# Sheet2.net
KiCad netlist of a schematic drawn in Altium Designer
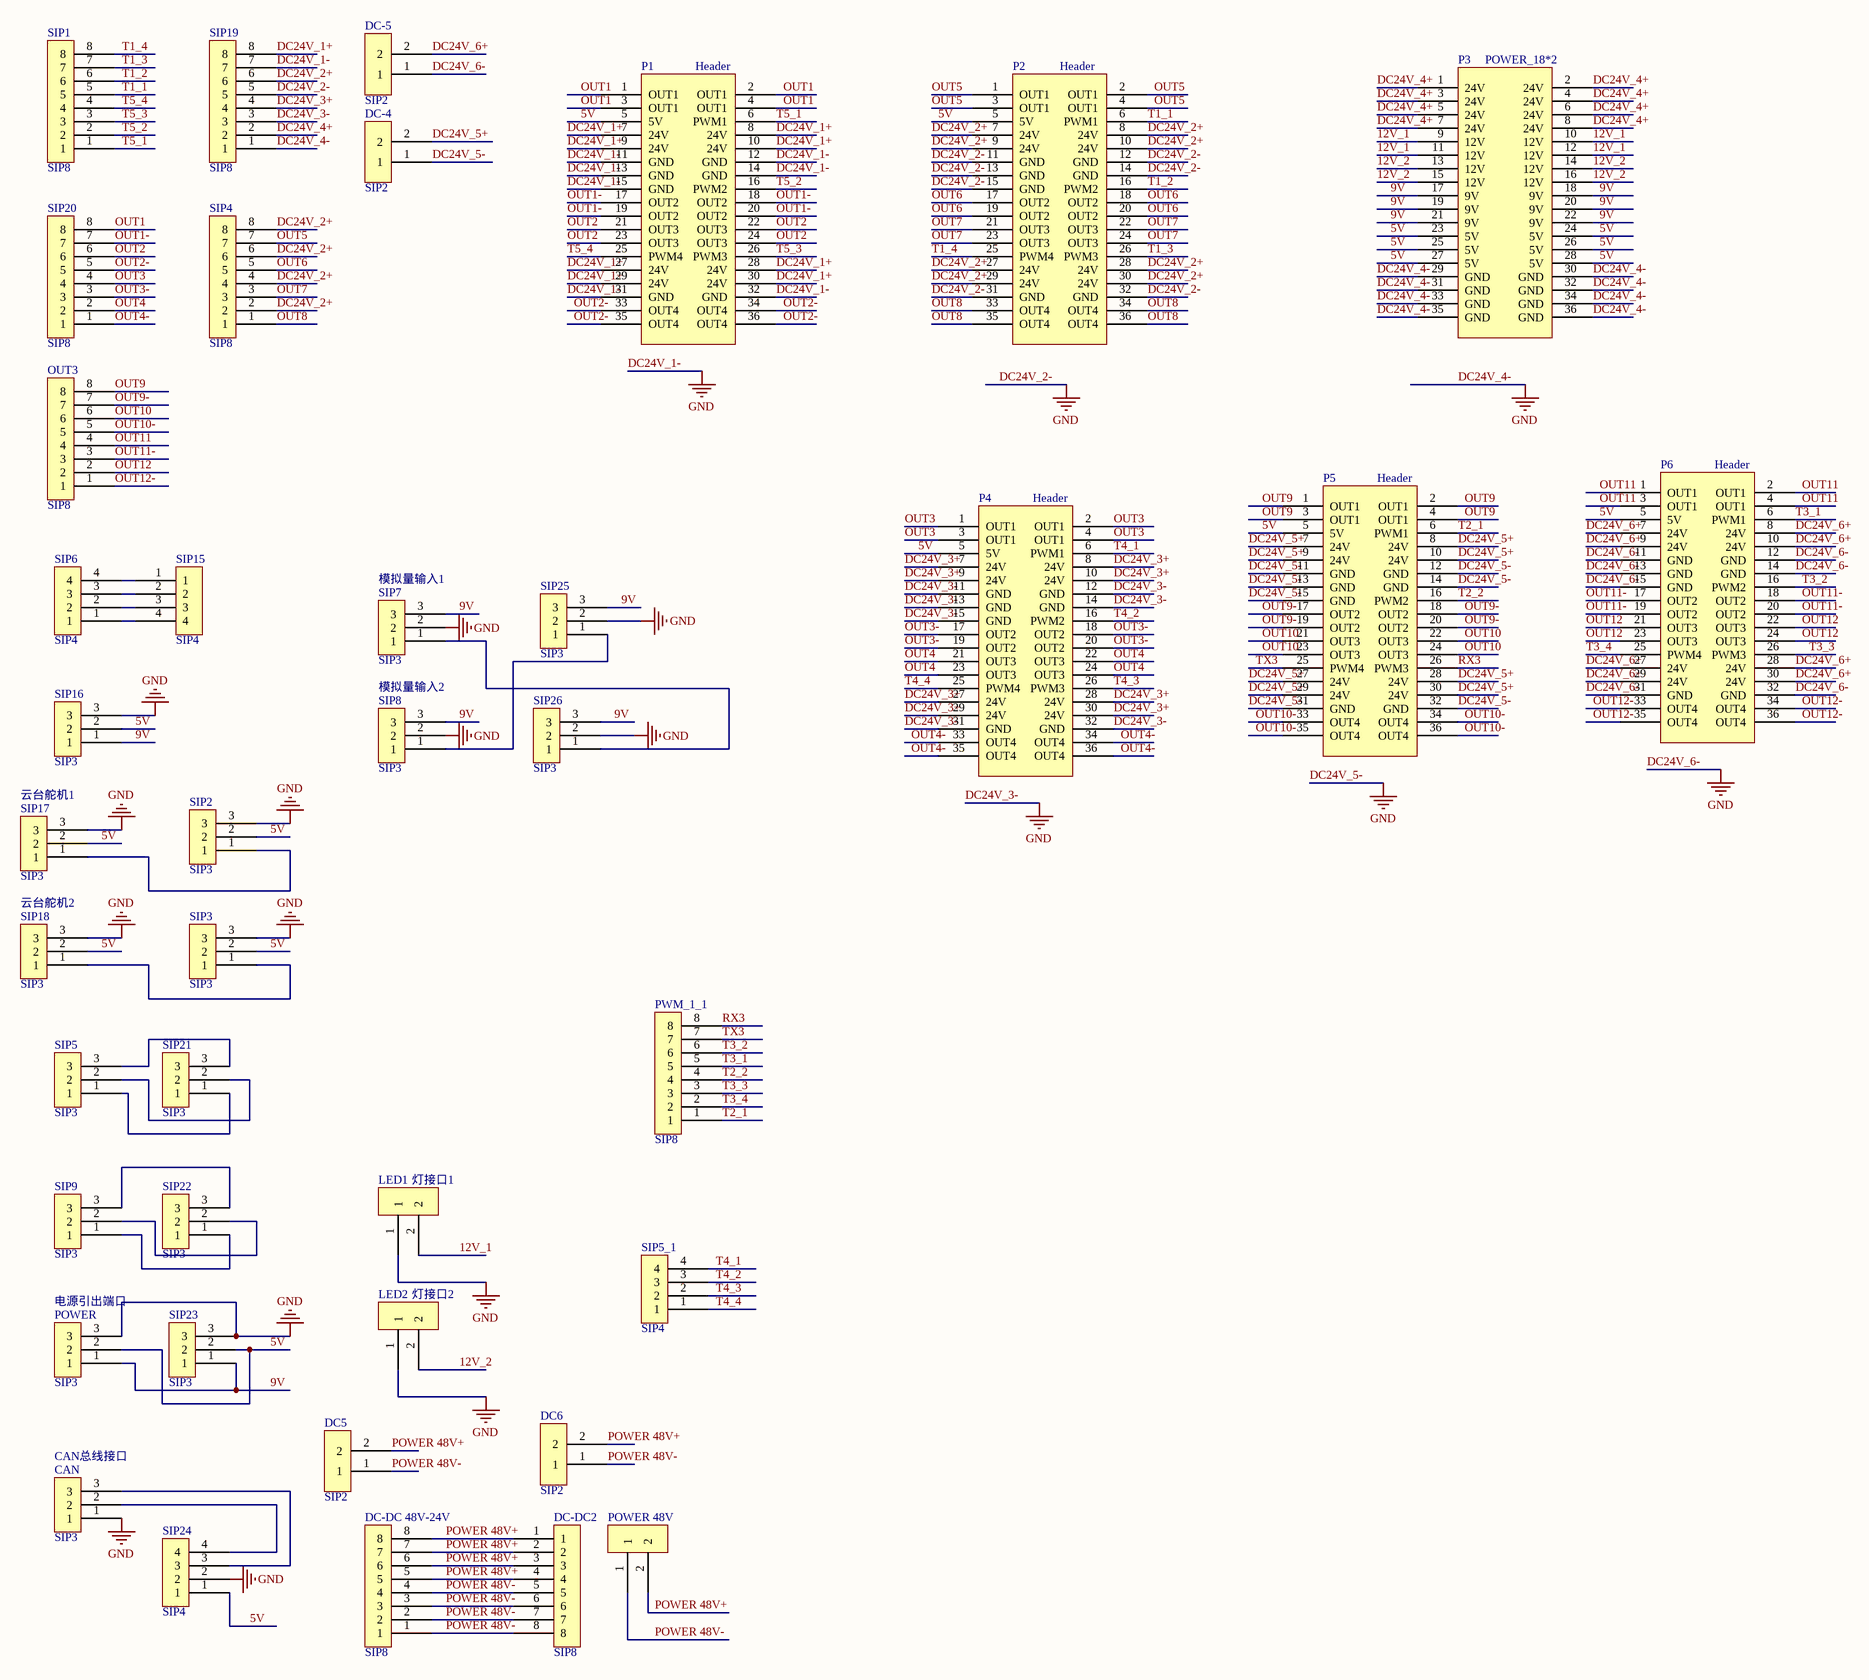
[diagram p0: Sheet2.SchDoc]

(export (version "E")
  (design (tool "Eeschema 10.0.6"))
  (components
    (comp (ref "CAN") (value "SIP3") (footprint "SIP3") (libsource (lib "qudong") (part "SIP3")))
    (comp (ref "DC-4") (value "SIP2") (footprint "DIP2-3MM-K") (libsource (lib "qudong") (part "SIP2")))
    (comp (ref "DC-5") (value "SIP2") (footprint "DIP2-3MM-K") (libsource (lib "qudong") (part "SIP2")))
    (comp (ref "DC-DC 48V-24V")
      (value "SIP8")
      (footprint "DIP8-3MM")
      (libsource (lib "qudong") (part "SIP8"))
    )
    (comp (ref "DC-DC2") (value "SIP8") (footprint "DIP8-3MM") (libsource (lib "") (part "SIP8_1")))
    (comp (ref "DC5") (value "SIP2") (footprint "DIP2-3MM-K") (libsource (lib "qudong") (part "SIP2")))
    (comp (ref "DC6") (value "SIP2") (footprint "DIP2-3MM-K") (libsource (lib "qudong") (part "SIP2")))
    (comp (ref "LED1") (value "SIP2") (footprint "SIP2-3MM") (libsource (lib "") (part "SIP2_1")))
    (comp (ref "LED2") (value "SIP2") (footprint "SIP2-3MM") (libsource (lib "") (part "SIP2_1")))
    (comp (ref "OUT3") (value "SIP8") (footprint "DIP8-3MM") (libsource (lib "qudong") (part "SIP8")))
    (comp (ref "P1") (value "Header") (footprint "DIP36-3.96MM") (libsource (lib "qudong") (part "Header")))
    (comp (ref "P2") (value "Header") (footprint "DIP36-3.96MM") (libsource (lib "qudong") (part "Header")))
    (comp (ref "P3")
      (value "POWER_18*2")
      (footprint "DIP36-3.96MM")
      (libsource (lib "qudong") (part "POWER_18*2"))
    )
    (comp (ref "P4") (value "Header") (footprint "DIP36-3.96MM") (libsource (lib "qudong") (part "Header")))
    (comp (ref "P5") (value "Header") (footprint "DIP36-3.96MM") (libsource (lib "qudong") (part "Header")))
    (comp (ref "P6") (value "Header") (footprint "DIP36-3.96MM") (libsource (lib "qudong") (part "Header")))
    (comp (ref "POWER") (value "SIP3") (footprint "SIP3") (libsource (lib "qudong") (part "SIP3")))
    (comp (ref "POWER 48V") (value "SIP2") (footprint "SIP2-3MM") (libsource (lib "") (part "SIP2_1")))
    (comp (ref "PWM_1_1") (value "SIP8") (footprint "SIP8") (libsource (lib "qudong") (part "SIP8")))
    (comp (ref "SIP1") (value "SIP8") (footprint "SIP8") (libsource (lib "qudong") (part "SIP8")))
    (comp (ref "SIP2") (value "SIP3") (footprint "SIP3") (libsource (lib "qudong") (part "SIP3")))
    (comp (ref "SIP3") (value "SIP3") (footprint "SIP3") (libsource (lib "qudong") (part "SIP3")))
    (comp (ref "SIP4") (value "SIP8") (footprint "DIP8-3MM") (libsource (lib "qudong") (part "SIP8")))
    (comp (ref "SIP5") (value "SIP3") (footprint "SIP3") (libsource (lib "qudong") (part "SIP3")))
    (comp (ref "SIP5_1") (value "SIP4") (footprint "SIP4") (libsource (lib "qudong") (part "SIP4")))
    (comp (ref "SIP6") (value "SIP4") (footprint "SIP4") (libsource (lib "qudong") (part "SIP4")))
    (comp (ref "SIP7") (value "SIP3") (footprint "SIP3") (libsource (lib "qudong") (part "SIP3")))
    (comp (ref "SIP8") (value "SIP3") (footprint "SIP3") (libsource (lib "qudong") (part "SIP3")))
    (comp (ref "SIP9") (value "SIP3") (footprint "SIP3") (libsource (lib "qudong") (part "SIP3")))
    (comp (ref "SIP15") (value "SIP4") (footprint "SIP4") (libsource (lib "") (part "SIP4_1")))
    (comp (ref "SIP16") (value "SIP3") (footprint "SIP3") (libsource (lib "qudong") (part "SIP3")))
    (comp (ref "SIP17") (value "SIP3") (footprint "SIP3") (libsource (lib "qudong") (part "SIP3")))
    (comp (ref "SIP18") (value "SIP3") (footprint "SIP3") (libsource (lib "qudong") (part "SIP3")))
    (comp (ref "SIP19") (value "SIP8") (footprint "DIP8-3MM") (libsource (lib "qudong") (part "SIP8")))
    (comp (ref "SIP20") (value "SIP8") (footprint "DIP8-3MM") (libsource (lib "qudong") (part "SIP8")))
    (comp (ref "SIP21") (value "SIP3") (footprint "SIP3") (libsource (lib "qudong") (part "SIP3")))
    (comp (ref "SIP22") (value "SIP3") (footprint "SIP3") (libsource (lib "qudong") (part "SIP3")))
    (comp (ref "SIP23") (value "SIP3") (footprint "SIP3") (libsource (lib "qudong") (part "SIP3")))
    (comp (ref "SIP24") (value "SIP4") (footprint "SIP4") (libsource (lib "qudong") (part "SIP4")))
    (comp (ref "SIP25") (value "SIP3") (footprint "SIP3") (libsource (lib "qudong") (part "SIP3")))
    (comp (ref "SIP26") (value "SIP3") (footprint "SIP3") (libsource (lib "qudong") (part "SIP3")))
  )
  (nets
    (net (code "1") (name "/5V") (class "Default")
      (node (ref "P1") (pin "5") (pinfunction "5V_5") (pintype "passive"))
      (node (ref "P2") (pin "5") (pinfunction "5V_5") (pintype "passive"))
      (node (ref "P3") (pin "23") (pinfunction "5V_23") (pintype "passive"))
      (node (ref "P3") (pin "24") (pinfunction "5V_24") (pintype "passive"))
      (node (ref "P3") (pin "25") (pinfunction "5V_25") (pintype "passive"))
      (node (ref "P3") (pin "26") (pinfunction "5V_26") (pintype "passive"))
      (node (ref "P3") (pin "27") (pinfunction "5V_27") (pintype "passive"))
      (node (ref "P3") (pin "28") (pinfunction "5V_28") (pintype "passive"))
      (node (ref "P4") (pin "5") (pinfunction "5V_5") (pintype "passive"))
      (node (ref "P5") (pin "5") (pinfunction "5V_5") (pintype "passive"))
      (node (ref "P6") (pin "5") (pinfunction "5V_5") (pintype "passive"))
      (node (ref "POWER") (pin "2") (pinfunction "2_2") (pintype "passive"))
      (node (ref "SIP16") (pin "2") (pinfunction "2_2") (pintype "passive"))
      (node (ref "SIP17") (pin "2") (pinfunction "2_2") (pintype "passive"))
      (node (ref "SIP18") (pin "2") (pinfunction "2_2") (pintype "passive"))
      (node (ref "SIP2") (pin "2") (pinfunction "2_2") (pintype "passive"))
      (node (ref "SIP23") (pin "2") (pinfunction "2_2") (pintype "passive"))
      (node (ref "SIP24") (pin "1") (pinfunction "1_1") (pintype "passive"))
      (node (ref "SIP3") (pin "2") (pinfunction "2_2") (pintype "passive"))
    )
    (net (code "2") (name "/9V") (class "Default")
      (node (ref "P3") (pin "17") (pinfunction "9V_17") (pintype "passive"))
      (node (ref "P3") (pin "18") (pinfunction "9V_18") (pintype "passive"))
      (node (ref "P3") (pin "19") (pinfunction "9V_19") (pintype "passive"))
      (node (ref "P3") (pin "20") (pinfunction "9V_20") (pintype "passive"))
      (node (ref "P3") (pin "21") (pinfunction "9V_21") (pintype "passive"))
      (node (ref "P3") (pin "22") (pinfunction "9V_22") (pintype "passive"))
      (node (ref "POWER") (pin "1") (pinfunction "1_1") (pintype "passive"))
      (node (ref "SIP16") (pin "1") (pinfunction "1_1") (pintype "passive"))
      (node (ref "SIP23") (pin "1") (pinfunction "1_1") (pintype "passive"))
      (node (ref "SIP25") (pin "3") (pinfunction "3_3") (pintype "passive"))
      (node (ref "SIP26") (pin "3") (pinfunction "3_3") (pintype "passive"))
      (node (ref "SIP7") (pin "3") (pinfunction "3_3") (pintype "passive"))
      (node (ref "SIP8") (pin "3") (pinfunction "3_3") (pintype "passive"))
    )
    (net (code "3") (name "/12V_1") (class "Default")
      (node (ref "LED1") (pin "2") (pinfunction "2_2") (pintype "passive"))
      (node (ref "P3") (pin "10") (pinfunction "12V_10") (pintype "passive"))
      (node (ref "P3") (pin "11") (pinfunction "12V_11") (pintype "passive"))
      (node (ref "P3") (pin "12") (pinfunction "12V_12") (pintype "passive"))
      (node (ref "P3") (pin "9") (pinfunction "12V_9") (pintype "passive"))
    )
    (net (code "4") (name "/12V_2") (class "Default")
      (node (ref "LED2") (pin "2") (pinfunction "2_2") (pintype "passive"))
      (node (ref "P3") (pin "13") (pinfunction "12V_13") (pintype "passive"))
      (node (ref "P3") (pin "14") (pinfunction "12V_14") (pintype "passive"))
      (node (ref "P3") (pin "15") (pinfunction "12V_15") (pintype "passive"))
      (node (ref "P3") (pin "16") (pinfunction "12V_16") (pintype "passive"))
    )
    (net (code "5") (name "/DC24V_1+") (class "Default")
      (node (ref "P1") (pin "10") (pinfunction "24V_10") (pintype "passive"))
      (node (ref "P1") (pin "27") (pinfunction "24V_27") (pintype "passive"))
      (node (ref "P1") (pin "28") (pinfunction "24V_28") (pintype "passive"))
      (node (ref "P1") (pin "29") (pinfunction "24V_29") (pintype "passive"))
      (node (ref "P1") (pin "30") (pinfunction "24V_30") (pintype "passive"))
      (node (ref "P1") (pin "7") (pinfunction "24V_7") (pintype "passive"))
      (node (ref "P1") (pin "8") (pinfunction "24V_8") (pintype "passive"))
      (node (ref "P1") (pin "9") (pinfunction "24V_9") (pintype "passive"))
      (node (ref "SIP19") (pin "8") (pinfunction "8_8") (pintype "passive"))
    )
    (net (code "6") (name "/DC24V_2+") (class "Default")
      (node (ref "P2") (pin "10") (pinfunction "24V_10") (pintype "passive"))
      (node (ref "P2") (pin "27") (pinfunction "24V_27") (pintype "passive"))
      (node (ref "P2") (pin "28") (pinfunction "24V_28") (pintype "passive"))
      (node (ref "P2") (pin "29") (pinfunction "24V_29") (pintype "passive"))
      (node (ref "P2") (pin "30") (pinfunction "24V_30") (pintype "passive"))
      (node (ref "P2") (pin "7") (pinfunction "24V_7") (pintype "passive"))
      (node (ref "P2") (pin "8") (pinfunction "24V_8") (pintype "passive"))
      (node (ref "P2") (pin "9") (pinfunction "24V_9") (pintype "passive"))
      (node (ref "SIP19") (pin "6") (pinfunction "6_6") (pintype "passive"))
      (node (ref "SIP4") (pin "2") (pinfunction "2_2") (pintype "passive"))
      (node (ref "SIP4") (pin "4") (pinfunction "4_4") (pintype "passive"))
      (node (ref "SIP4") (pin "6") (pinfunction "6_6") (pintype "passive"))
      (node (ref "SIP4") (pin "8") (pinfunction "8_8") (pintype "passive"))
    )
    (net (code "7") (name "/DC24V_3+") (class "Default")
      (node (ref "P4") (pin "10") (pinfunction "24V_10") (pintype "passive"))
      (node (ref "P4") (pin "27") (pinfunction "24V_27") (pintype "passive"))
      (node (ref "P4") (pin "28") (pinfunction "24V_28") (pintype "passive"))
      (node (ref "P4") (pin "29") (pinfunction "24V_29") (pintype "passive"))
      (node (ref "P4") (pin "30") (pinfunction "24V_30") (pintype "passive"))
      (node (ref "P4") (pin "7") (pinfunction "24V_7") (pintype "passive"))
      (node (ref "P4") (pin "8") (pinfunction "24V_8") (pintype "passive"))
      (node (ref "P4") (pin "9") (pinfunction "24V_9") (pintype "passive"))
      (node (ref "SIP19") (pin "4") (pinfunction "4_4") (pintype "passive"))
    )
    (net (code "8") (name "/DC24V_4+") (class "Default")
      (node (ref "P3") (pin "1") (pinfunction "24V_1") (pintype "passive"))
      (node (ref "P3") (pin "2") (pinfunction "24V_2") (pintype "passive"))
      (node (ref "P3") (pin "3") (pinfunction "24V_3") (pintype "passive"))
      (node (ref "P3") (pin "4") (pinfunction "24V_4") (pintype "passive"))
      (node (ref "P3") (pin "5") (pinfunction "24V_5") (pintype "passive"))
      (node (ref "P3") (pin "6") (pinfunction "24V_6") (pintype "passive"))
      (node (ref "P3") (pin "7") (pinfunction "24V_7") (pintype "passive"))
      (node (ref "P3") (pin "8") (pinfunction "24V_8") (pintype "passive"))
      (node (ref "SIP19") (pin "2") (pinfunction "2_2") (pintype "passive"))
    )
    (net (code "9") (name "/DC24V_5+") (class "Default")
      (node (ref "DC-4") (pin "2") (pinfunction "2_2") (pintype "passive"))
      (node (ref "P5") (pin "10") (pinfunction "24V_10") (pintype "passive"))
      (node (ref "P5") (pin "27") (pinfunction "24V_27") (pintype "passive"))
      (node (ref "P5") (pin "28") (pinfunction "24V_28") (pintype "passive"))
      (node (ref "P5") (pin "29") (pinfunction "24V_29") (pintype "passive"))
      (node (ref "P5") (pin "30") (pinfunction "24V_30") (pintype "passive"))
      (node (ref "P5") (pin "7") (pinfunction "24V_7") (pintype "passive"))
      (node (ref "P5") (pin "8") (pinfunction "24V_8") (pintype "passive"))
      (node (ref "P5") (pin "9") (pinfunction "24V_9") (pintype "passive"))
    )
    (net (code "10") (name "/DC24V_6+") (class "Default")
      (node (ref "DC-5") (pin "2") (pinfunction "2_2") (pintype "passive"))
      (node (ref "P6") (pin "10") (pinfunction "24V_10") (pintype "passive"))
      (node (ref "P6") (pin "27") (pinfunction "24V_27") (pintype "passive"))
      (node (ref "P6") (pin "28") (pinfunction "24V_28") (pintype "passive"))
      (node (ref "P6") (pin "29") (pinfunction "24V_29") (pintype "passive"))
      (node (ref "P6") (pin "30") (pinfunction "24V_30") (pintype "passive"))
      (node (ref "P6") (pin "7") (pinfunction "24V_7") (pintype "passive"))
      (node (ref "P6") (pin "8") (pinfunction "24V_8") (pintype "passive"))
      (node (ref "P6") (pin "9") (pinfunction "24V_9") (pintype "passive"))
    )
    (net (code "11") (name "/OUT1") (class "Default")
      (node (ref "P1") (pin "1") (pinfunction "OUT1_1") (pintype "passive"))
      (node (ref "P1") (pin "2") (pinfunction "OUT1_2") (pintype "passive"))
      (node (ref "P1") (pin "3") (pinfunction "OUT1_3") (pintype "passive"))
      (node (ref "P1") (pin "4") (pinfunction "OUT1_4") (pintype "passive"))
      (node (ref "SIP20") (pin "8") (pinfunction "8_8") (pintype "passive"))
    )
    (net (code "12") (name "/OUT1-") (class "Default")
      (node (ref "P1") (pin "17") (pinfunction "OUT2_17") (pintype "passive"))
      (node (ref "P1") (pin "18") (pinfunction "OUT2_18") (pintype "passive"))
      (node (ref "P1") (pin "19") (pinfunction "OUT2_19") (pintype "passive"))
      (node (ref "P1") (pin "20") (pinfunction "OUT2_20") (pintype "passive"))
      (node (ref "SIP20") (pin "7") (pinfunction "7_7") (pintype "passive"))
    )
    (net (code "13") (name "/OUT2") (class "Default")
      (node (ref "P1") (pin "21") (pinfunction "OUT3_21") (pintype "passive"))
      (node (ref "P1") (pin "22") (pinfunction "OUT3_22") (pintype "passive"))
      (node (ref "P1") (pin "23") (pinfunction "OUT3_23") (pintype "passive"))
      (node (ref "P1") (pin "24") (pinfunction "OUT3_24") (pintype "passive"))
      (node (ref "SIP20") (pin "6") (pinfunction "6_6") (pintype "passive"))
    )
    (net (code "14") (name "/OUT2-") (class "Default")
      (node (ref "P1") (pin "33") (pinfunction "OUT4_33") (pintype "passive"))
      (node (ref "P1") (pin "34") (pinfunction "OUT4_34") (pintype "passive"))
      (node (ref "P1") (pin "35") (pinfunction "OUT4_35") (pintype "passive"))
      (node (ref "P1") (pin "36") (pinfunction "OUT4_36") (pintype "passive"))
      (node (ref "SIP20") (pin "5") (pinfunction "5_5") (pintype "passive"))
    )
    (net (code "15") (name "/OUT3") (class "Default")
      (node (ref "P4") (pin "1") (pinfunction "OUT1_1") (pintype "passive"))
      (node (ref "P4") (pin "2") (pinfunction "OUT1_2") (pintype "passive"))
      (node (ref "P4") (pin "3") (pinfunction "OUT1_3") (pintype "passive"))
      (node (ref "P4") (pin "4") (pinfunction "OUT1_4") (pintype "passive"))
      (node (ref "SIP20") (pin "4") (pinfunction "4_4") (pintype "passive"))
    )
    (net (code "16") (name "/OUT3-") (class "Default")
      (node (ref "P4") (pin "17") (pinfunction "OUT2_17") (pintype "passive"))
      (node (ref "P4") (pin "18") (pinfunction "OUT2_18") (pintype "passive"))
      (node (ref "P4") (pin "19") (pinfunction "OUT2_19") (pintype "passive"))
      (node (ref "P4") (pin "20") (pinfunction "OUT2_20") (pintype "passive"))
      (node (ref "SIP20") (pin "3") (pinfunction "3_3") (pintype "passive"))
    )
    (net (code "17") (name "/OUT4") (class "Default")
      (node (ref "P4") (pin "21") (pinfunction "OUT3_21") (pintype "passive"))
      (node (ref "P4") (pin "22") (pinfunction "OUT3_22") (pintype "passive"))
      (node (ref "P4") (pin "23") (pinfunction "OUT3_23") (pintype "passive"))
      (node (ref "P4") (pin "24") (pinfunction "OUT3_24") (pintype "passive"))
      (node (ref "SIP20") (pin "2") (pinfunction "2_2") (pintype "passive"))
    )
    (net (code "18") (name "/OUT4-") (class "Default")
      (node (ref "P4") (pin "33") (pinfunction "OUT4_33") (pintype "passive"))
      (node (ref "P4") (pin "34") (pinfunction "OUT4_34") (pintype "passive"))
      (node (ref "P4") (pin "35") (pinfunction "OUT4_35") (pintype "passive"))
      (node (ref "P4") (pin "36") (pinfunction "OUT4_36") (pintype "passive"))
      (node (ref "SIP20") (pin "1") (pinfunction "1_1") (pintype "passive"))
    )
    (net (code "19") (name "/OUT5") (class "Default")
      (node (ref "P2") (pin "1") (pinfunction "OUT1_1") (pintype "passive"))
      (node (ref "P2") (pin "2") (pinfunction "OUT1_2") (pintype "passive"))
      (node (ref "P2") (pin "3") (pinfunction "OUT1_3") (pintype "passive"))
      (node (ref "P2") (pin "4") (pinfunction "OUT1_4") (pintype "passive"))
      (node (ref "SIP4") (pin "7") (pinfunction "7_7") (pintype "passive"))
    )
    (net (code "20") (name "/OUT6") (class "Default")
      (node (ref "P2") (pin "17") (pinfunction "OUT2_17") (pintype "passive"))
      (node (ref "P2") (pin "18") (pinfunction "OUT2_18") (pintype "passive"))
      (node (ref "P2") (pin "19") (pinfunction "OUT2_19") (pintype "passive"))
      (node (ref "P2") (pin "20") (pinfunction "OUT2_20") (pintype "passive"))
      (node (ref "SIP4") (pin "5") (pinfunction "5_5") (pintype "passive"))
    )
    (net (code "21") (name "/OUT7") (class "Default")
      (node (ref "P2") (pin "21") (pinfunction "OUT3_21") (pintype "passive"))
      (node (ref "P2") (pin "22") (pinfunction "OUT3_22") (pintype "passive"))
      (node (ref "P2") (pin "23") (pinfunction "OUT3_23") (pintype "passive"))
      (node (ref "P2") (pin "24") (pinfunction "OUT3_24") (pintype "passive"))
      (node (ref "SIP4") (pin "3") (pinfunction "3_3") (pintype "passive"))
    )
    (net (code "22") (name "/OUT8") (class "Default")
      (node (ref "P2") (pin "33") (pinfunction "OUT4_33") (pintype "passive"))
      (node (ref "P2") (pin "34") (pinfunction "OUT4_34") (pintype "passive"))
      (node (ref "P2") (pin "35") (pinfunction "OUT4_35") (pintype "passive"))
      (node (ref "P2") (pin "36") (pinfunction "OUT4_36") (pintype "passive"))
      (node (ref "SIP4") (pin "1") (pinfunction "1_1") (pintype "passive"))
    )
    (net (code "23") (name "/OUT9") (class "Default")
      (node (ref "OUT3") (pin "8") (pinfunction "8_8") (pintype "passive"))
      (node (ref "P5") (pin "1") (pinfunction "OUT1_1") (pintype "passive"))
      (node (ref "P5") (pin "2") (pinfunction "OUT1_2") (pintype "passive"))
      (node (ref "P5") (pin "3") (pinfunction "OUT1_3") (pintype "passive"))
      (node (ref "P5") (pin "4") (pinfunction "OUT1_4") (pintype "passive"))
    )
    (net (code "24") (name "/OUT9-") (class "Default")
      (node (ref "OUT3") (pin "7") (pinfunction "7_7") (pintype "passive"))
      (node (ref "P5") (pin "17") (pinfunction "OUT2_17") (pintype "passive"))
      (node (ref "P5") (pin "18") (pinfunction "OUT2_18") (pintype "passive"))
      (node (ref "P5") (pin "19") (pinfunction "OUT2_19") (pintype "passive"))
      (node (ref "P5") (pin "20") (pinfunction "OUT2_20") (pintype "passive"))
    )
    (net (code "25") (name "/OUT10") (class "Default")
      (node (ref "OUT3") (pin "6") (pinfunction "6_6") (pintype "passive"))
      (node (ref "P5") (pin "21") (pinfunction "OUT3_21") (pintype "passive"))
      (node (ref "P5") (pin "22") (pinfunction "OUT3_22") (pintype "passive"))
      (node (ref "P5") (pin "23") (pinfunction "OUT3_23") (pintype "passive"))
      (node (ref "P5") (pin "24") (pinfunction "OUT3_24") (pintype "passive"))
    )
    (net (code "26") (name "/OUT10-") (class "Default")
      (node (ref "OUT3") (pin "5") (pinfunction "5_5") (pintype "passive"))
      (node (ref "P5") (pin "33") (pinfunction "OUT4_33") (pintype "passive"))
      (node (ref "P5") (pin "34") (pinfunction "OUT4_34") (pintype "passive"))
      (node (ref "P5") (pin "35") (pinfunction "OUT4_35") (pintype "passive"))
      (node (ref "P5") (pin "36") (pinfunction "OUT4_36") (pintype "passive"))
    )
    (net (code "27") (name "/OUT11") (class "Default")
      (node (ref "OUT3") (pin "4") (pinfunction "4_4") (pintype "passive"))
      (node (ref "P6") (pin "1") (pinfunction "OUT1_1") (pintype "passive"))
      (node (ref "P6") (pin "2") (pinfunction "OUT1_2") (pintype "passive"))
      (node (ref "P6") (pin "3") (pinfunction "OUT1_3") (pintype "passive"))
      (node (ref "P6") (pin "4") (pinfunction "OUT1_4") (pintype "passive"))
    )
    (net (code "28") (name "/OUT11-") (class "Default")
      (node (ref "OUT3") (pin "3") (pinfunction "3_3") (pintype "passive"))
      (node (ref "P6") (pin "17") (pinfunction "OUT2_17") (pintype "passive"))
      (node (ref "P6") (pin "18") (pinfunction "OUT2_18") (pintype "passive"))
      (node (ref "P6") (pin "19") (pinfunction "OUT2_19") (pintype "passive"))
      (node (ref "P6") (pin "20") (pinfunction "OUT2_20") (pintype "passive"))
    )
    (net (code "29") (name "/OUT12") (class "Default")
      (node (ref "OUT3") (pin "2") (pinfunction "2_2") (pintype "passive"))
      (node (ref "P6") (pin "21") (pinfunction "OUT3_21") (pintype "passive"))
      (node (ref "P6") (pin "22") (pinfunction "OUT3_22") (pintype "passive"))
      (node (ref "P6") (pin "23") (pinfunction "OUT3_23") (pintype "passive"))
      (node (ref "P6") (pin "24") (pinfunction "OUT3_24") (pintype "passive"))
    )
    (net (code "30") (name "/OUT12-") (class "Default")
      (node (ref "OUT3") (pin "1") (pinfunction "1_1") (pintype "passive"))
      (node (ref "P6") (pin "33") (pinfunction "OUT4_33") (pintype "passive"))
      (node (ref "P6") (pin "34") (pinfunction "OUT4_34") (pintype "passive"))
      (node (ref "P6") (pin "35") (pinfunction "OUT4_35") (pintype "passive"))
      (node (ref "P6") (pin "36") (pinfunction "OUT4_36") (pintype "passive"))
    )
    (net (code "31") (name "/POWER 48V+") (class "Default")
      (node (ref "DC-DC 48V-24V") (pin "5") (pinfunction "5_5") (pintype "passive"))
      (node (ref "DC-DC 48V-24V") (pin "6") (pinfunction "6_6") (pintype "passive"))
      (node (ref "DC-DC 48V-24V") (pin "7") (pinfunction "7_7") (pintype "passive"))
      (node (ref "DC-DC 48V-24V") (pin "8") (pinfunction "8_8") (pintype "passive"))
      (node (ref "DC-DC2") (pin "1") (pinfunction "1_1") (pintype "passive"))
      (node (ref "DC-DC2") (pin "2") (pinfunction "2_2") (pintype "passive"))
      (node (ref "DC-DC2") (pin "3") (pinfunction "3_3") (pintype "passive"))
      (node (ref "DC-DC2") (pin "4") (pinfunction "4_4") (pintype "passive"))
      (node (ref "DC5") (pin "2") (pinfunction "2_2") (pintype "passive"))
      (node (ref "DC6") (pin "2") (pinfunction "2_2") (pintype "passive"))
      (node (ref "POWER 48V") (pin "2") (pinfunction "2_2") (pintype "passive"))
    )
    (net (code "32") (name "/POWER 48V-") (class "Default")
      (node (ref "DC-DC 48V-24V") (pin "1") (pinfunction "1_1") (pintype "passive"))
      (node (ref "DC-DC 48V-24V") (pin "2") (pinfunction "2_2") (pintype "passive"))
      (node (ref "DC-DC 48V-24V") (pin "3") (pinfunction "3_3") (pintype "passive"))
      (node (ref "DC-DC 48V-24V") (pin "4") (pinfunction "4_4") (pintype "passive"))
      (node (ref "DC-DC2") (pin "5") (pinfunction "5_5") (pintype "passive"))
      (node (ref "DC-DC2") (pin "6") (pinfunction "6_6") (pintype "passive"))
      (node (ref "DC-DC2") (pin "7") (pinfunction "7_7") (pintype "passive"))
      (node (ref "DC-DC2") (pin "8") (pinfunction "8_8") (pintype "passive"))
      (node (ref "DC5") (pin "1") (pinfunction "1_1") (pintype "passive"))
      (node (ref "DC6") (pin "1") (pinfunction "1_1") (pintype "passive"))
      (node (ref "POWER 48V") (pin "1") (pinfunction "1_1") (pintype "passive"))
    )
    (net (code "33") (name "/RX3") (class "Default")
      (node (ref "P5") (pin "26") (pinfunction "PWM3_26") (pintype "passive"))
      (node (ref "PWM_1_1") (pin "8") (pinfunction "8_8") (pintype "passive"))
    )
    (net (code "34") (name "/T1_1") (class "Default")
      (node (ref "P2") (pin "6") (pinfunction "PWM1_6") (pintype "passive"))
      (node (ref "SIP1") (pin "5") (pinfunction "5_5") (pintype "passive"))
    )
    (net (code "35") (name "/T1_2") (class "Default")
      (node (ref "P2") (pin "16") (pinfunction "PWM2_16") (pintype "passive"))
      (node (ref "SIP1") (pin "6") (pinfunction "6_6") (pintype "passive"))
    )
    (net (code "36") (name "/T1_3") (class "Default")
      (node (ref "P2") (pin "26") (pinfunction "PWM3_26") (pintype "passive"))
      (node (ref "SIP1") (pin "7") (pinfunction "7_7") (pintype "passive"))
    )
    (net (code "37") (name "/T1_4") (class "Default")
      (node (ref "P2") (pin "25") (pinfunction "PWM4_25") (pintype "passive"))
      (node (ref "SIP1") (pin "8") (pinfunction "8_8") (pintype "passive"))
    )
    (net (code "38") (name "/T2_1") (class "Default")
      (node (ref "P5") (pin "6") (pinfunction "PWM1_6") (pintype "passive"))
      (node (ref "PWM_1_1") (pin "1") (pinfunction "1_1") (pintype "passive"))
    )
    (net (code "39") (name "/T2_2") (class "Default")
      (node (ref "P5") (pin "16") (pinfunction "PWM2_16") (pintype "passive"))
      (node (ref "PWM_1_1") (pin "4") (pinfunction "4_4") (pintype "passive"))
    )
    (net (code "40") (name "/T3_1") (class "Default")
      (node (ref "P6") (pin "6") (pinfunction "PWM1_6") (pintype "passive"))
      (node (ref "PWM_1_1") (pin "5") (pinfunction "5_5") (pintype "passive"))
    )
    (net (code "41") (name "/T3_2") (class "Default")
      (node (ref "P6") (pin "16") (pinfunction "PWM2_16") (pintype "passive"))
      (node (ref "PWM_1_1") (pin "6") (pinfunction "6_6") (pintype "passive"))
    )
    (net (code "42") (name "/T3_3") (class "Default")
      (node (ref "P6") (pin "26") (pinfunction "PWM3_26") (pintype "passive"))
      (node (ref "PWM_1_1") (pin "3") (pinfunction "3_3") (pintype "passive"))
    )
    (net (code "43") (name "/T3_4") (class "Default")
      (node (ref "P6") (pin "25") (pinfunction "PWM4_25") (pintype "passive"))
      (node (ref "PWM_1_1") (pin "2") (pinfunction "2_2") (pintype "passive"))
    )
    (net (code "44") (name "/T4_1") (class "Default")
      (node (ref "P4") (pin "6") (pinfunction "PWM1_6") (pintype "passive"))
      (node (ref "SIP5_1") (pin "4") (pinfunction "4_4") (pintype "passive"))
    )
    (net (code "45") (name "/T4_2") (class "Default")
      (node (ref "P4") (pin "16") (pinfunction "PWM2_16") (pintype "passive"))
      (node (ref "SIP5_1") (pin "3") (pinfunction "3_3") (pintype "passive"))
    )
    (net (code "46") (name "/T4_3") (class "Default")
      (node (ref "P4") (pin "26") (pinfunction "PWM3_26") (pintype "passive"))
      (node (ref "SIP5_1") (pin "2") (pinfunction "2_2") (pintype "passive"))
    )
    (net (code "47") (name "/T4_4") (class "Default")
      (node (ref "P4") (pin "25") (pinfunction "PWM4_25") (pintype "passive"))
      (node (ref "SIP5_1") (pin "1") (pinfunction "1_1") (pintype "passive"))
    )
    (net (code "48") (name "/T5_1") (class "Default")
      (node (ref "P1") (pin "6") (pinfunction "PWM1_6") (pintype "passive"))
      (node (ref "SIP1") (pin "1") (pinfunction "1_1") (pintype "passive"))
    )
    (net (code "49") (name "/T5_2") (class "Default")
      (node (ref "P1") (pin "16") (pinfunction "PWM2_16") (pintype "passive"))
      (node (ref "SIP1") (pin "2") (pinfunction "2_2") (pintype "passive"))
    )
    (net (code "50") (name "/T5_3") (class "Default")
      (node (ref "P1") (pin "26") (pinfunction "PWM3_26") (pintype "passive"))
      (node (ref "SIP1") (pin "3") (pinfunction "3_3") (pintype "passive"))
    )
    (net (code "51") (name "/T5_4") (class "Default")
      (node (ref "P1") (pin "25") (pinfunction "PWM4_25") (pintype "passive"))
      (node (ref "SIP1") (pin "4") (pinfunction "4_4") (pintype "passive"))
    )
    (net (code "52") (name "/TX3") (class "Default")
      (node (ref "P5") (pin "25") (pinfunction "PWM4_25") (pintype "passive"))
      (node (ref "PWM_1_1") (pin "7") (pinfunction "7_7") (pintype "passive"))
    )
    (net (code "53") (name "GND") (class "Default")
      (node (ref "CAN") (pin "1") (pinfunction "1_1") (pintype "passive"))
      (node (ref "DC-4") (pin "1") (pinfunction "1_1") (pintype "passive"))
      (node (ref "DC-5") (pin "1") (pinfunction "1_1") (pintype "passive"))
      (node (ref "LED1") (pin "1") (pinfunction "1_1") (pintype "passive"))
      (node (ref "LED2") (pin "1") (pinfunction "1_1") (pintype "passive"))
      (node (ref "P1") (pin "11") (pinfunction "GND_11") (pintype "passive"))
      (node (ref "P1") (pin "12") (pinfunction "GND_12") (pintype "passive"))
      (node (ref "P1") (pin "13") (pinfunction "GND_13") (pintype "passive"))
      (node (ref "P1") (pin "14") (pinfunction "GND_14") (pintype "passive"))
      (node (ref "P1") (pin "15") (pinfunction "GND_15") (pintype "passive"))
      (node (ref "P1") (pin "31") (pinfunction "GND_31") (pintype "passive"))
      (node (ref "P1") (pin "32") (pinfunction "GND_32") (pintype "passive"))
      (node (ref "P2") (pin "11") (pinfunction "GND_11") (pintype "passive"))
      (node (ref "P2") (pin "12") (pinfunction "GND_12") (pintype "passive"))
      (node (ref "P2") (pin "13") (pinfunction "GND_13") (pintype "passive"))
      (node (ref "P2") (pin "14") (pinfunction "GND_14") (pintype "passive"))
      (node (ref "P2") (pin "15") (pinfunction "GND_15") (pintype "passive"))
      (node (ref "P2") (pin "31") (pinfunction "GND_31") (pintype "passive"))
      (node (ref "P2") (pin "32") (pinfunction "GND_32") (pintype "passive"))
      (node (ref "P3") (pin "29") (pinfunction "GND_29") (pintype "passive"))
      (node (ref "P3") (pin "30") (pinfunction "GND_30") (pintype "passive"))
      (node (ref "P3") (pin "31") (pinfunction "GND_31") (pintype "passive"))
      (node (ref "P3") (pin "32") (pinfunction "GND_32") (pintype "passive"))
      (node (ref "P3") (pin "33") (pinfunction "GND_33") (pintype "passive"))
      (node (ref "P3") (pin "34") (pinfunction "GND_34") (pintype "passive"))
      (node (ref "P3") (pin "35") (pinfunction "GND_35") (pintype "passive"))
      (node (ref "P3") (pin "36") (pinfunction "GND_36") (pintype "passive"))
      (node (ref "P4") (pin "11") (pinfunction "GND_11") (pintype "passive"))
      (node (ref "P4") (pin "12") (pinfunction "GND_12") (pintype "passive"))
      (node (ref "P4") (pin "13") (pinfunction "GND_13") (pintype "passive"))
      (node (ref "P4") (pin "14") (pinfunction "GND_14") (pintype "passive"))
      (node (ref "P4") (pin "15") (pinfunction "GND_15") (pintype "passive"))
      (node (ref "P4") (pin "31") (pinfunction "GND_31") (pintype "passive"))
      (node (ref "P4") (pin "32") (pinfunction "GND_32") (pintype "passive"))
      (node (ref "P5") (pin "11") (pinfunction "GND_11") (pintype "passive"))
      (node (ref "P5") (pin "12") (pinfunction "GND_12") (pintype "passive"))
      (node (ref "P5") (pin "13") (pinfunction "GND_13") (pintype "passive"))
      (node (ref "P5") (pin "14") (pinfunction "GND_14") (pintype "passive"))
      (node (ref "P5") (pin "15") (pinfunction "GND_15") (pintype "passive"))
      (node (ref "P5") (pin "31") (pinfunction "GND_31") (pintype "passive"))
      (node (ref "P5") (pin "32") (pinfunction "GND_32") (pintype "passive"))
      (node (ref "P6") (pin "11") (pinfunction "GND_11") (pintype "passive"))
      (node (ref "P6") (pin "12") (pinfunction "GND_12") (pintype "passive"))
      (node (ref "P6") (pin "13") (pinfunction "GND_13") (pintype "passive"))
      (node (ref "P6") (pin "14") (pinfunction "GND_14") (pintype "passive"))
      (node (ref "P6") (pin "15") (pinfunction "GND_15") (pintype "passive"))
      (node (ref "P6") (pin "31") (pinfunction "GND_31") (pintype "passive"))
      (node (ref "P6") (pin "32") (pinfunction "GND_32") (pintype "passive"))
      (node (ref "POWER") (pin "3") (pinfunction "3_3") (pintype "passive"))
      (node (ref "SIP16") (pin "3") (pinfunction "3_3") (pintype "passive"))
      (node (ref "SIP17") (pin "3") (pinfunction "3_3") (pintype "passive"))
      (node (ref "SIP18") (pin "3") (pinfunction "3_3") (pintype "passive"))
      (node (ref "SIP19") (pin "1") (pinfunction "1_1") (pintype "passive"))
      (node (ref "SIP19") (pin "3") (pinfunction "3_3") (pintype "passive"))
      (node (ref "SIP19") (pin "5") (pinfunction "5_5") (pintype "passive"))
      (node (ref "SIP19") (pin "7") (pinfunction "7_7") (pintype "passive"))
      (node (ref "SIP2") (pin "3") (pinfunction "3_3") (pintype "passive"))
      (node (ref "SIP23") (pin "3") (pinfunction "3_3") (pintype "passive"))
      (node (ref "SIP24") (pin "2") (pinfunction "2_2") (pintype "passive"))
      (node (ref "SIP25") (pin "2") (pinfunction "2_2") (pintype "passive"))
      (node (ref "SIP26") (pin "2") (pinfunction "2_2") (pintype "passive"))
      (node (ref "SIP3") (pin "3") (pinfunction "3_3") (pintype "passive"))
      (node (ref "SIP7") (pin "2") (pinfunction "2_2") (pintype "passive"))
      (node (ref "SIP8") (pin "2") (pinfunction "2_2") (pintype "passive"))
    )
    (net (code "54") (name "Net-(CAN-Pad2)") (class "Default")
      (node (ref "CAN") (pin "2") (pinfunction "2_2") (pintype "passive"))
      (node (ref "SIP24") (pin "4") (pinfunction "4_4") (pintype "passive"))
    )
    (net (code "55") (name "Net-(CAN-Pad3)") (class "Default")
      (node (ref "CAN") (pin "3") (pinfunction "3_3") (pintype "passive"))
      (node (ref "SIP24") (pin "3") (pinfunction "3_3") (pintype "passive"))
    )
    (net (code "56") (name "Net-(SIP15-Pad1)") (class "Default")
      (node (ref "SIP15") (pin "1") (pinfunction "1_1") (pintype "passive"))
      (node (ref "SIP6") (pin "4") (pinfunction "4_4") (pintype "passive"))
    )
    (net (code "57") (name "Net-(SIP15-Pad2)") (class "Default")
      (node (ref "SIP15") (pin "2") (pinfunction "2_2") (pintype "passive"))
      (node (ref "SIP6") (pin "3") (pinfunction "3_3") (pintype "passive"))
    )
    (net (code "58") (name "Net-(SIP15-Pad3)") (class "Default")
      (node (ref "SIP15") (pin "3") (pinfunction "3_3") (pintype "passive"))
      (node (ref "SIP6") (pin "2") (pinfunction "2_2") (pintype "passive"))
    )
    (net (code "59") (name "Net-(SIP15-Pad4)") (class "Default")
      (node (ref "SIP15") (pin "4") (pinfunction "4_4") (pintype "passive"))
      (node (ref "SIP6") (pin "1") (pinfunction "1_1") (pintype "passive"))
    )
    (net (code "60") (name "Net-(SIP17-Pad1)") (class "Default")
      (node (ref "SIP17") (pin "1") (pinfunction "1_1") (pintype "passive"))
      (node (ref "SIP2") (pin "1") (pinfunction "1_1") (pintype "passive"))
    )
    (net (code "61") (name "Net-(SIP18-Pad1)") (class "Default")
      (node (ref "SIP18") (pin "1") (pinfunction "1_1") (pintype "passive"))
      (node (ref "SIP3") (pin "1") (pinfunction "1_1") (pintype "passive"))
    )
    (net (code "62") (name "Net-(SIP21-Pad1)") (class "Default")
      (node (ref "SIP21") (pin "1") (pinfunction "1_1") (pintype "passive"))
      (node (ref "SIP5") (pin "1") (pinfunction "1_1") (pintype "passive"))
    )
    (net (code "63") (name "Net-(SIP21-Pad2)") (class "Default")
      (node (ref "SIP21") (pin "2") (pinfunction "2_2") (pintype "passive"))
      (node (ref "SIP5") (pin "2") (pinfunction "2_2") (pintype "passive"))
    )
    (net (code "64") (name "Net-(SIP21-Pad3)") (class "Default")
      (node (ref "SIP21") (pin "3") (pinfunction "3_3") (pintype "passive"))
      (node (ref "SIP5") (pin "3") (pinfunction "3_3") (pintype "passive"))
    )
    (net (code "65") (name "Net-(SIP22-Pad1)") (class "Default")
      (node (ref "SIP22") (pin "1") (pinfunction "1_1") (pintype "passive"))
      (node (ref "SIP9") (pin "1") (pinfunction "1_1") (pintype "passive"))
    )
    (net (code "66") (name "Net-(SIP22-Pad2)") (class "Default")
      (node (ref "SIP22") (pin "2") (pinfunction "2_2") (pintype "passive"))
      (node (ref "SIP9") (pin "2") (pinfunction "2_2") (pintype "passive"))
    )
    (net (code "67") (name "Net-(SIP22-Pad3)") (class "Default")
      (node (ref "SIP22") (pin "3") (pinfunction "3_3") (pintype "passive"))
      (node (ref "SIP9") (pin "3") (pinfunction "3_3") (pintype "passive"))
    )
    (net (code "68") (name "Net-(SIP25-Pad1)") (class "Default")
      (node (ref "SIP25") (pin "1") (pinfunction "1_1") (pintype "passive"))
      (node (ref "SIP8") (pin "1") (pinfunction "1_1") (pintype "passive"))
    )
    (net (code "69") (name "Net-(SIP26-Pad1)") (class "Default")
      (node (ref "SIP26") (pin "1") (pinfunction "1_1") (pintype "passive"))
      (node (ref "SIP7") (pin "1") (pinfunction "1_1") (pintype "passive"))
    )
  )
)
